# FPGA_Peripherals_Control.net
KiCad netlist of a schematic drawn in Altium Designer
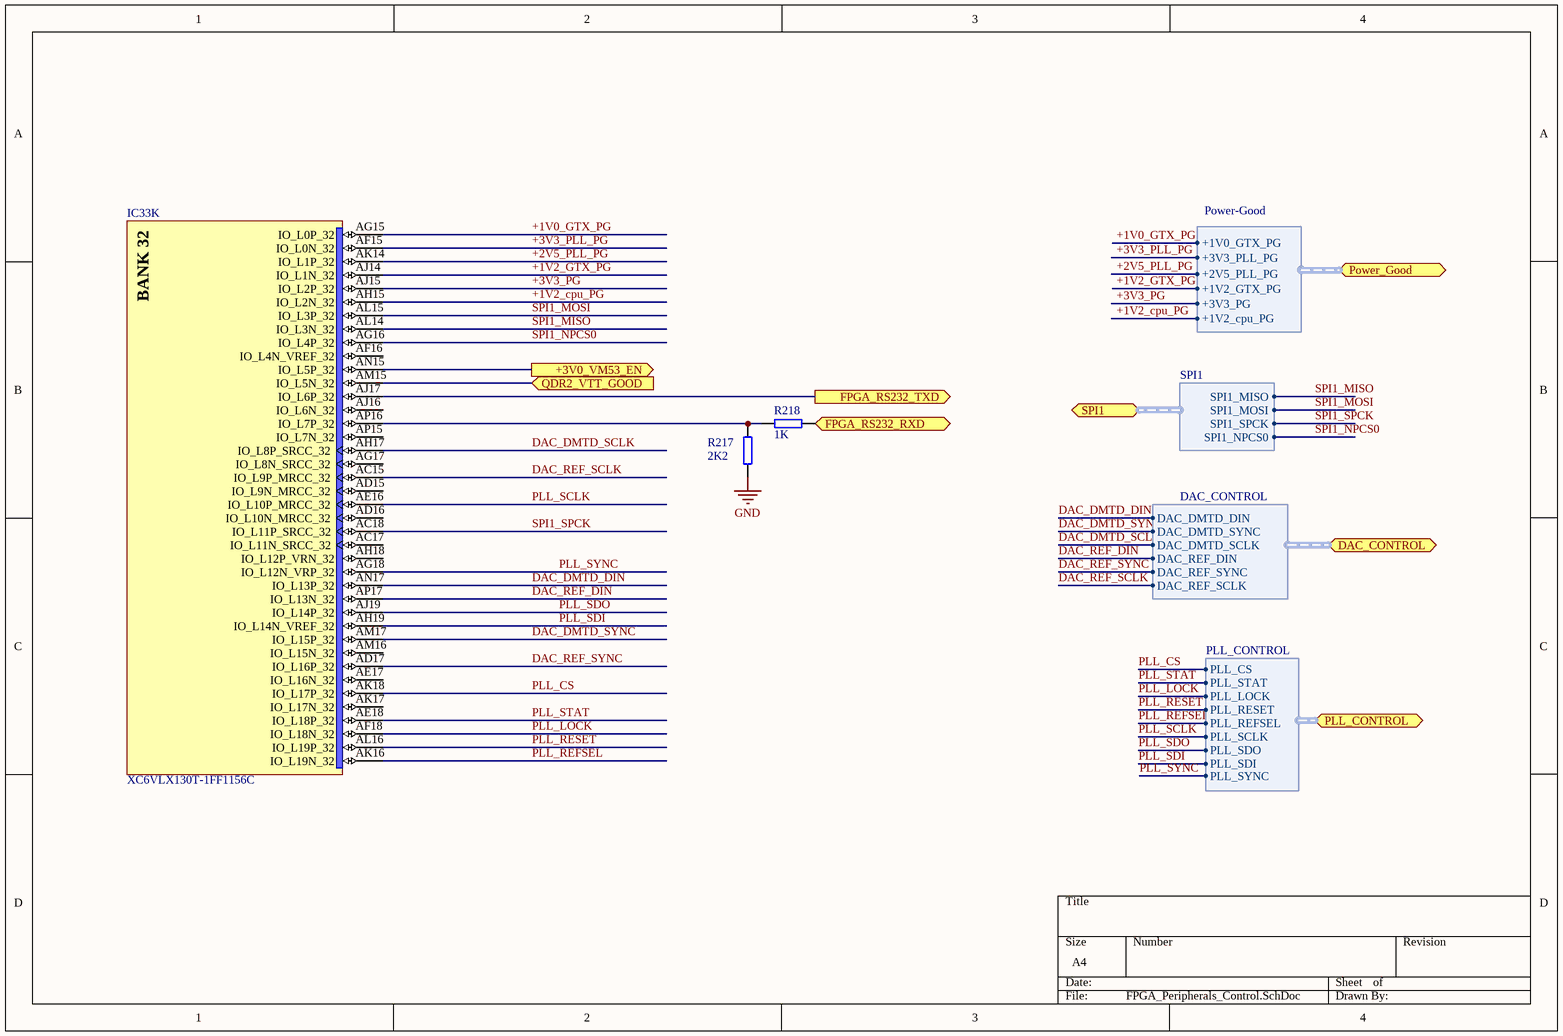
[diagram p0: FPGA_Peripherals_Control.SchDoc]

(export (version "E")
  (design (tool "Eeschema 10.0.6"))
  (components
    (comp (ref "IC33")
      (value "XC6VLX130T-1FF1156C")
      (footprint "FF1156")
      (fields (field (name "PUBLISHER") "Altium Limited"))
      (libsource (lib "Xilinx Virtex-6") (part "XC6VLX130T-1FF1156C"))
    )
    (comp (ref "R217")
      (value "2K2")
      (footprint "0402")
      (description "SMD Resistor")
      (fields (field (name "TOLERANCE") "±1%"))
      (libsource (lib "wr_switch") (part "RES_SMD"))
    )
    (comp (ref "R218")
      (value "1K")
      (footprint "0402")
      (description "SMD Resistor")
      (fields (field (name "TOLERANCE") "±1%"))
      (libsource (lib "wr_switch") (part "RES_SMD"))
    )
  )
  (nets
    (net (code "5") (name "/+1V0_GTX_PG") (class "Default")
      (node (ref "IC33") (pin "AG15") (pinfunction "IO_L0P_32_AG15") (pintype "bidirectional"))
    )
    (net (code "6") (name "/+1V2_GTX_PG") (class "Default")
      (node (ref "IC33") (pin "AJ14") (pinfunction "IO_L1N_32_AJ14") (pintype "bidirectional"))
    )
    (net (code "7") (name "/+1V2_cpu_PG") (class "Default")
      (node (ref "IC33") (pin "AH15") (pinfunction "IO_L2N_32_AH15") (pintype "bidirectional"))
    )
    (net (code "8") (name "/+2V5_PLL_PG") (class "Default")
      (node (ref "IC33") (pin "AK14") (pinfunction "IO_L1P_32_AK14") (pintype "bidirectional"))
    )
    (net (code "9") (name "/+3V0_VM53_EN") (class "Default")
      (node (ref "IC33") (pin "AN15") (pinfunction "IO_L5P_32_AN15") (pintype "bidirectional"))
    )
    (net (code "10") (name "/+3V3_PG") (class "Default")
      (node (ref "IC33") (pin "AJ15") (pinfunction "IO_L2P_32_AJ15") (pintype "bidirectional"))
    )
    (net (code "11") (name "/+3V3_PLL_PG") (class "Default")
      (node (ref "IC33") (pin "AF15") (pinfunction "IO_L0N_32_AF15") (pintype "bidirectional"))
    )
    (net (code "12") (name "/DAC_DMTD_DIN") (class "Default")
      (node (ref "IC33") (pin "AN17") (pinfunction "IO_L13P_32_AN17") (pintype "bidirectional"))
    )
    (net (code "13") (name "/DAC_DMTD_SCLK") (class "Default")
      (node (ref "IC33") (pin "AH17") (pinfunction "IO_L8P_SRCC_32_AH17") (pintype "bidirectional"))
    )
    (net (code "14") (name "/DAC_DMTD_SYNC") (class "Default")
      (node (ref "IC33") (pin "AM17") (pinfunction "IO_L15P_32_AM17") (pintype "bidirectional"))
    )
    (net (code "15") (name "/DAC_REF_DIN") (class "Default")
      (node (ref "IC33") (pin "AP17") (pinfunction "IO_L13N_32_AP17") (pintype "bidirectional"))
    )
    (net (code "16") (name "/DAC_REF_SCLK") (class "Default")
      (node (ref "IC33") (pin "AC15") (pinfunction "IO_L9P_MRCC_32_AC15") (pintype "bidirectional"))
    )
    (net (code "17") (name "/DAC_REF_SYNC") (class "Default")
      (node (ref "IC33") (pin "AD17") (pinfunction "IO_L16P_32_AD17") (pintype "bidirectional"))
    )
    (net (code "18") (name "/FPGA_RS232_RXD") (class "Default")
      (node (ref "R218") (pin "1") (pinfunction "1_1") (pintype "passive"))
    )
    (net (code "19") (name "/FPGA_RS232_TXD") (class "Default")
      (node (ref "IC33") (pin "AJ17") (pinfunction "IO_L6P_32_AJ17") (pintype "bidirectional"))
    )
    (net (code "20") (name "/PLL_CS") (class "Default")
      (node (ref "IC33") (pin "AK18") (pinfunction "IO_L17P_32_AK18") (pintype "bidirectional"))
    )
    (net (code "21") (name "/PLL_LOCK") (class "Default")
      (node (ref "IC33") (pin "AF18") (pinfunction "IO_L18N_32_AF18") (pintype "bidirectional"))
    )
    (net (code "22") (name "/PLL_REFSEL") (class "Default")
      (node (ref "IC33") (pin "AK16") (pinfunction "IO_L19N_32_AK16") (pintype "bidirectional"))
    )
    (net (code "23") (name "/PLL_RESET") (class "Default")
      (node (ref "IC33") (pin "AL16") (pinfunction "IO_L19P_32_AL16") (pintype "bidirectional"))
    )
    (net (code "24") (name "/PLL_SCLK") (class "Default")
      (node (ref "IC33") (pin "AE16") (pinfunction "IO_L10P_MRCC_32_AE16") (pintype "bidirectional"))
    )
    (net (code "25") (name "/PLL_SDI") (class "Default")
      (node (ref "IC33") (pin "AH19") (pinfunction "IO_L14N_VREF_32_AH19") (pintype "bidirectional"))
    )
    (net (code "26") (name "/PLL_SDO") (class "Default")
      (node (ref "IC33") (pin "AJ19") (pinfunction "IO_L14P_32_AJ19") (pintype "bidirectional"))
    )
    (net (code "27") (name "/PLL_STAT") (class "Default")
      (node (ref "IC33") (pin "AE18") (pinfunction "IO_L18P_32_AE18") (pintype "bidirectional"))
    )
    (net (code "28") (name "/PLL_SYNC") (class "Default")
      (node (ref "IC33") (pin "AG18") (pinfunction "IO_L12N_VRP_32_AG18") (pintype "bidirectional"))
    )
    (net (code "29") (name "/QDR2_VTT_GOOD") (class "Default")
      (node (ref "IC33") (pin "AM15") (pinfunction "IO_L5N_32_AM15") (pintype "bidirectional"))
    )
    (net (code "30") (name "/SPI1_MISO") (class "Default")
      (node (ref "IC33") (pin "AL14") (pinfunction "IO_L3N_32_AL14") (pintype "bidirectional"))
    )
    (net (code "31") (name "/SPI1_MOSI") (class "Default")
      (node (ref "IC33") (pin "AL15") (pinfunction "IO_L3P_32_AL15") (pintype "bidirectional"))
    )
    (net (code "32") (name "/SPI1_NPCS0") (class "Default")
      (node (ref "IC33") (pin "AG16") (pinfunction "IO_L4P_32_AG16") (pintype "bidirectional"))
    )
    (net (code "33") (name "/SPI1_SPCK") (class "Default")
      (node (ref "IC33") (pin "AC18") (pinfunction "IO_L11P_SRCC_32_AC18") (pintype "bidirectional"))
    )
    (net (code "38") (name "GND") (class "Default")
      (node (ref "R217") (pin "2") (pinfunction "2_2") (pintype "passive"))
    )
    (net (code "39") (name "Net-(IC33K-IO_L7P_32)") (class "Default")
      (node (ref "IC33") (pin "AP16") (pinfunction "IO_L7P_32_AP16") (pintype "bidirectional"))
      (node (ref "R217") (pin "1") (pinfunction "1_1") (pintype "passive"))
      (node (ref "R218") (pin "2") (pinfunction "2_2") (pintype "passive"))
    )
    (net (code "40") (name "unconnected-(IC33K-IO_L4N_VREF_32-PadAF16)") (class "Default")
      (node (ref "IC33") (pin "AF16") (pinfunction "IO_L4N_VREF_32_AF16") (pintype "bidirectional"))
    )
    (net (code "41") (name "unconnected-(IC33K-IO_L6N_32-PadAJ16)") (class "Default")
      (node (ref "IC33") (pin "AJ16") (pinfunction "IO_L6N_32_AJ16") (pintype "bidirectional"))
    )
    (net (code "42") (name "unconnected-(IC33K-IO_L7N_32-PadAP15)") (class "Default")
      (node (ref "IC33") (pin "AP15") (pinfunction "IO_L7N_32_AP15") (pintype "bidirectional"))
    )
    (net (code "43") (name "unconnected-(IC33K-IO_L8N_SRCC_32-PadAG17)") (class "Default")
      (node (ref "IC33") (pin "AG17") (pinfunction "IO_L8N_SRCC_32_AG17") (pintype "bidirectional"))
    )
    (net (code "44") (name "unconnected-(IC33K-IO_L9N_MRCC_32-PadAD15)") (class "Default")
      (node (ref "IC33") (pin "AD15") (pinfunction "IO_L9N_MRCC_32_AD15") (pintype "bidirectional"))
    )
    (net (code "45") (name "unconnected-(IC33K-IO_L10N_MRCC_32-PadAD16)") (class "Default")
      (node (ref "IC33") (pin "AD16") (pinfunction "IO_L10N_MRCC_32_AD16") (pintype "bidirectional"))
    )
    (net (code "46") (name "unconnected-(IC33K-IO_L11N_SRCC_32-PadAC17)") (class "Default")
      (node (ref "IC33") (pin "AC17") (pinfunction "IO_L11N_SRCC_32_AC17") (pintype "bidirectional"))
    )
    (net (code "47") (name "unconnected-(IC33K-IO_L12P_VRN_32-PadAH18)") (class "Default")
      (node (ref "IC33") (pin "AH18") (pinfunction "IO_L12P_VRN_32_AH18") (pintype "bidirectional"))
    )
    (net (code "48") (name "unconnected-(IC33K-IO_L15N_32-PadAM16)") (class "Default")
      (node (ref "IC33") (pin "AM16") (pinfunction "IO_L15N_32_AM16") (pintype "bidirectional"))
    )
    (net (code "49") (name "unconnected-(IC33K-IO_L16N_32-PadAE17)") (class "Default")
      (node (ref "IC33") (pin "AE17") (pinfunction "IO_L16N_32_AE17") (pintype "bidirectional"))
    )
    (net (code "50") (name "unconnected-(IC33K-IO_L17N_32-PadAK17)") (class "Default")
      (node (ref "IC33") (pin "AK17") (pinfunction "IO_L17N_32_AK17") (pintype "bidirectional"))
    )
  )
)
